# LEDBatterychargeIndicatorCircuit.net
KiCad netlist of a schematic drawn in EAGLE
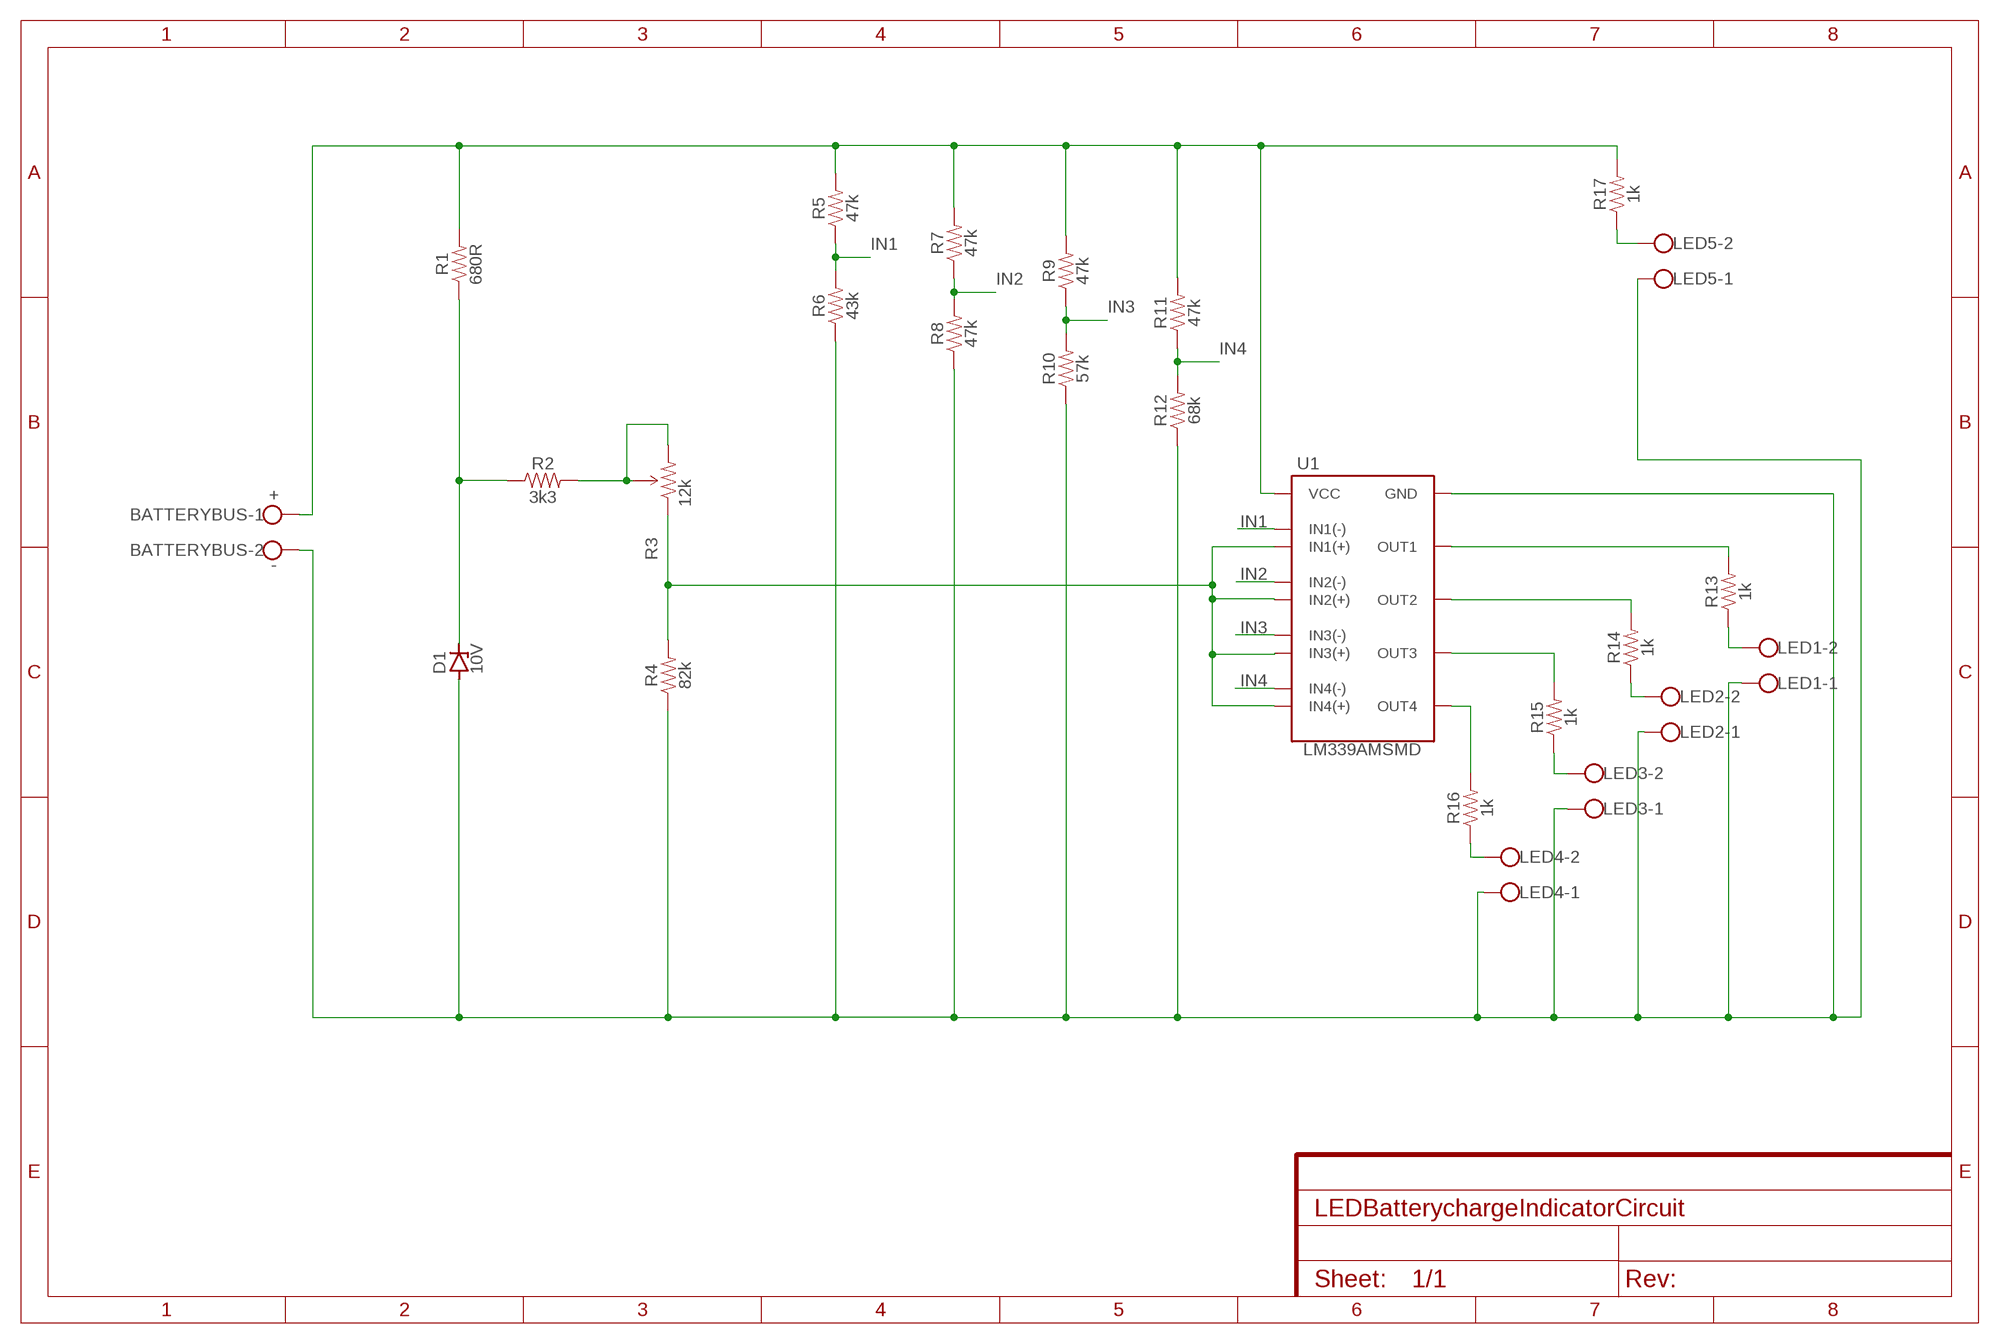
[diagram p0: schematic, sheet 1]

(export (version "E")
  (design (tool "Eeschema 10.0.6"))
  (components
    (comp (ref "BATTERYBUS")
      (value "W237-102")
      (footprint "eagle-import:W237-102")
      (fields (field (name "MPN") "237-102"))
      (libsource (lib "eagle-import") (part "W237-102"))
    )
    (comp (ref "D1")
      (value "10V")
      (footprint "eagle-import:F126Z12")
      (libsource (lib "eagle-import") (part "ZENER-DIODEF126-12"))
    )
    (comp (ref "LED1")
      (value "W237-102")
      (footprint "eagle-import:W237-102")
      (fields (field (name "MPN") "237-102"))
      (libsource (lib "eagle-import") (part "W237-102"))
    )
    (comp (ref "LED2")
      (value "W237-102")
      (footprint "eagle-import:W237-102")
      (fields (field (name "MPN") "237-102"))
      (libsource (lib "eagle-import") (part "W237-102"))
    )
    (comp (ref "LED3")
      (value "W237-102")
      (footprint "eagle-import:W237-102")
      (fields (field (name "MPN") "237-102"))
      (libsource (lib "eagle-import") (part "W237-102"))
    )
    (comp (ref "LED4")
      (value "W237-102")
      (footprint "eagle-import:W237-102")
      (fields (field (name "MPN") "237-102"))
      (libsource (lib "eagle-import") (part "W237-102"))
    )
    (comp (ref "LED5")
      (value "W237-102")
      (footprint "eagle-import:W237-102")
      (fields (field (name "MPN") "237-102"))
      (libsource (lib "eagle-import") (part "W237-102"))
    )
    (comp (ref "R1")
      (value "680R")
      (footprint "eagle-import:0805")
      (libsource (lib "eagle-import") (part "RESISTOR0805"))
    )
    (comp (ref "R2")
      (value "3k3")
      (footprint "eagle-import:0805")
      (libsource (lib "eagle-import") (part "RESISTOR0805"))
    )
    (comp (ref "R3")
      (value "12k")
      (footprint "eagle-import:TRIM_POT_PTH")
      (libsource (lib "eagle-import") (part "TRIMPOTPTH"))
    )
    (comp (ref "R4")
      (value "82k")
      (footprint "eagle-import:0805")
      (libsource (lib "eagle-import") (part "RESISTOR0805"))
    )
    (comp (ref "R5")
      (value "47k")
      (footprint "eagle-import:0805")
      (libsource (lib "eagle-import") (part "RESISTOR0805"))
    )
    (comp (ref "R6")
      (value "43k")
      (footprint "eagle-import:0805")
      (libsource (lib "eagle-import") (part "RESISTOR0805"))
    )
    (comp (ref "R7")
      (value "47k")
      (footprint "eagle-import:0805")
      (libsource (lib "eagle-import") (part "RESISTOR0805"))
    )
    (comp (ref "R8")
      (value "47k")
      (footprint "eagle-import:0805")
      (libsource (lib "eagle-import") (part "RESISTOR0805"))
    )
    (comp (ref "R9")
      (value "47k")
      (footprint "eagle-import:0805")
      (libsource (lib "eagle-import") (part "RESISTOR0805"))
    )
    (comp (ref "R10")
      (value "57k")
      (footprint "eagle-import:0805")
      (libsource (lib "eagle-import") (part "RESISTOR0805"))
    )
    (comp (ref "R11")
      (value "47k")
      (footprint "eagle-import:0805")
      (libsource (lib "eagle-import") (part "RESISTOR0805"))
    )
    (comp (ref "R12")
      (value "68k")
      (footprint "eagle-import:0805")
      (libsource (lib "eagle-import") (part "RESISTOR0805"))
    )
    (comp (ref "R13")
      (value "1k")
      (footprint "eagle-import:0805")
      (libsource (lib "eagle-import") (part "RESISTOR0805"))
    )
    (comp (ref "R14")
      (value "1k")
      (footprint "eagle-import:0805")
      (libsource (lib "eagle-import") (part "RESISTOR0805"))
    )
    (comp (ref "R15")
      (value "1k")
      (footprint "eagle-import:0805")
      (libsource (lib "eagle-import") (part "RESISTOR0805"))
    )
    (comp (ref "R16")
      (value "1k")
      (footprint "eagle-import:0805")
      (libsource (lib "eagle-import") (part "RESISTOR0805"))
    )
    (comp (ref "R17")
      (value "1k")
      (footprint "eagle-import:0805")
      (libsource (lib "eagle-import") (part "RESISTOR0805"))
    )
    (comp (ref "U1")
      (value "LM339AMSMD")
      (footprint "eagle-import:LM339AM")
      (libsource (lib "eagle-import") (part "LM339AMSMD"))
    )
  )
  (nets
    (net (code "1") (name "/IN1") (class "Default")
      (node (ref "R5") (pin "1") (pinfunction "1_1") (pintype "passive"))
      (node (ref "R6") (pin "2") (pinfunction "2_2") (pintype "passive"))
      (node (ref "U1") (pin "4") (pinfunction "IN1(-)_4") (pintype "input"))
    )
    (net (code "2") (name "/IN2") (class "Default")
      (node (ref "R7") (pin "1") (pinfunction "1_1") (pintype "passive"))
      (node (ref "R8") (pin "2") (pinfunction "2_2") (pintype "passive"))
      (node (ref "U1") (pin "6") (pinfunction "IN2(-)_6") (pintype "input"))
    )
    (net (code "3") (name "/IN3") (class "Default")
      (node (ref "R10") (pin "2") (pinfunction "2_2") (pintype "passive"))
      (node (ref "R9") (pin "1") (pinfunction "1_1") (pintype "passive"))
      (node (ref "U1") (pin "8") (pinfunction "IN3(-)_8") (pintype "input"))
    )
    (net (code "4") (name "/IN4") (class "Default")
      (node (ref "R11") (pin "1") (pinfunction "1_1") (pintype "passive"))
      (node (ref "R12") (pin "2") (pinfunction "2_2") (pintype "passive"))
      (node (ref "U1") (pin "10") (pinfunction "IN4(-)_10") (pintype "input"))
    )
    (net (code "5") (name "Net-(BATTERYBUSB-KL)") (class "Default")
      (node (ref "BATTERYBUS") (pin "2") (pinfunction "KL_2") (pintype "passive"))
      (node (ref "D1") (pin "A") (pinfunction "A_A") (pintype "passive"))
      (node (ref "LED1") (pin "1") (pinfunction "KL_1") (pintype "passive"))
      (node (ref "LED2") (pin "1") (pinfunction "KL_1") (pintype "passive"))
      (node (ref "LED3") (pin "1") (pinfunction "KL_1") (pintype "passive"))
      (node (ref "LED4") (pin "1") (pinfunction "KL_1") (pintype "passive"))
      (node (ref "LED5") (pin "1") (pinfunction "KL_1") (pintype "passive"))
      (node (ref "R10") (pin "1") (pinfunction "1_1") (pintype "passive"))
      (node (ref "R12") (pin "1") (pinfunction "1_1") (pintype "passive"))
      (node (ref "R4") (pin "1") (pinfunction "1_1") (pintype "passive"))
      (node (ref "R6") (pin "1") (pinfunction "1_1") (pintype "passive"))
      (node (ref "R8") (pin "1") (pinfunction "1_1") (pintype "passive"))
      (node (ref "U1") (pin "12") (pinfunction "GND_12") (pintype "power_in"))
    )
    (net (code "6") (name "Net-(D1-PadC)") (class "Default")
      (node (ref "D1") (pin "C") (pinfunction "C_C") (pintype "passive"))
      (node (ref "R1") (pin "1") (pinfunction "1_1") (pintype "passive"))
      (node (ref "R2") (pin "1") (pinfunction "1_1") (pintype "passive"))
    )
    (net (code "7") (name "Net-(LED1B-KL)") (class "Default")
      (node (ref "LED1") (pin "2") (pinfunction "KL_2") (pintype "passive"))
      (node (ref "R13") (pin "1") (pinfunction "1_1") (pintype "passive"))
    )
    (net (code "8") (name "Net-(LED2B-KL)") (class "Default")
      (node (ref "LED2") (pin "2") (pinfunction "KL_2") (pintype "passive"))
      (node (ref "R14") (pin "1") (pinfunction "1_1") (pintype "passive"))
    )
    (net (code "9") (name "Net-(LED3B-KL)") (class "Default")
      (node (ref "LED3") (pin "2") (pinfunction "KL_2") (pintype "passive"))
      (node (ref "R15") (pin "1") (pinfunction "1_1") (pintype "passive"))
    )
    (net (code "10") (name "Net-(LED4B-KL)") (class "Default")
      (node (ref "LED4") (pin "2") (pinfunction "KL_2") (pintype "passive"))
      (node (ref "R16") (pin "1") (pinfunction "1_1") (pintype "passive"))
    )
    (net (code "11") (name "Net-(LED5B-KL)") (class "Default")
      (node (ref "LED5") (pin "2") (pinfunction "KL_2") (pintype "passive"))
      (node (ref "R17") (pin "1") (pinfunction "1_1") (pintype "passive"))
    )
    (net (code "12") (name "Net-(R3-CCW)") (class "Default")
      (node (ref "R3") (pin "1") (pinfunction "CCW_1") (pintype "passive"))
      (node (ref "R4") (pin "2") (pinfunction "2_2") (pintype "passive"))
      (node (ref "U1") (pin "11") (pinfunction "IN4(+)_11") (pintype "input"))
      (node (ref "U1") (pin "5") (pinfunction "IN1(+)_5") (pintype "input"))
      (node (ref "U1") (pin "7") (pinfunction "IN2(+)_7") (pintype "input"))
      (node (ref "U1") (pin "9") (pinfunction "IN3(+)_9") (pintype "input"))
    )
    (net (code "13") (name "Net-(R3-CW)") (class "Default")
      (node (ref "R2") (pin "2") (pinfunction "2_2") (pintype "passive"))
      (node (ref "R3") (pin "2") (pinfunction "WIPER_2") (pintype "passive"))
      (node (ref "R3") (pin "3") (pinfunction "CW_3") (pintype "passive"))
    )
    (net (code "14") (name "Net-(U1-OUT1)") (class "Default")
      (node (ref "R13") (pin "2") (pinfunction "2_2") (pintype "passive"))
      (node (ref "U1") (pin "2") (pinfunction "OUT1_2") (pintype "output"))
    )
    (net (code "15") (name "Net-(U1-OUT2)") (class "Default")
      (node (ref "R14") (pin "2") (pinfunction "2_2") (pintype "passive"))
      (node (ref "U1") (pin "1") (pinfunction "OUT2_1") (pintype "output"))
    )
    (net (code "16") (name "Net-(U1-OUT3)") (class "Default")
      (node (ref "R15") (pin "2") (pinfunction "2_2") (pintype "passive"))
      (node (ref "U1") (pin "14") (pinfunction "OUT3_14") (pintype "output"))
    )
    (net (code "17") (name "Net-(U1-OUT4)") (class "Default")
      (node (ref "R16") (pin "2") (pinfunction "2_2") (pintype "passive"))
      (node (ref "U1") (pin "13") (pinfunction "OUT4_13") (pintype "output"))
    )
    (net (code "18") (name "Net-(U1-VCC)") (class "Default")
      (node (ref "R1") (pin "2") (pinfunction "2_2") (pintype "passive"))
      (node (ref "R11") (pin "2") (pinfunction "2_2") (pintype "passive"))
      (node (ref "R17") (pin "2") (pinfunction "2_2") (pintype "passive"))
      (node (ref "R5") (pin "2") (pinfunction "2_2") (pintype "passive"))
      (node (ref "R7") (pin "2") (pinfunction "2_2") (pintype "passive"))
      (node (ref "R9") (pin "2") (pinfunction "2_2") (pintype "passive"))
      (node (ref "U1") (pin "3") (pinfunction "VCC_3") (pintype "power_in"))
    )
    (net (code "19") (name "unconnected-(BATTERYBUSA-KL-Pad1)") (class "Default")
      (node (ref "BATTERYBUS") (pin "1") (pinfunction "KL_1") (pintype "passive"))
    )
  )
)
